# Programmer.net
KiCad netlist of a schematic drawn in Altium Designer
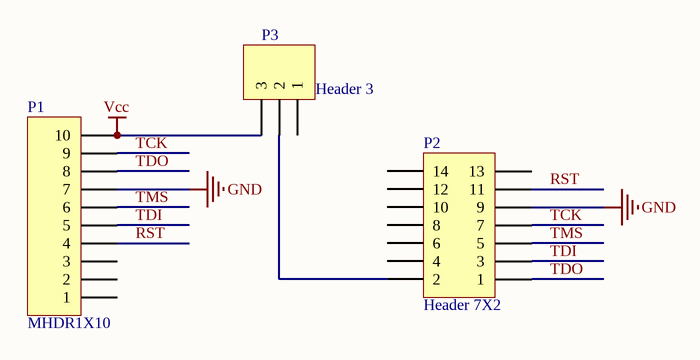
[diagram p0: Programmer.SchDoc]

(export (version "E")
  (design (tool "Eeschema 10.0.6"))
  (components
    (comp (ref "P1")
      (value "MHDR1X10")
      (footprint "MHDR1X10")
      (description "CONN HEADER RT ANG 50POS .050")
      (fields (field (name "MANUFACTURER") "Mill-Max Manufacturing Corp."))
      (libsource (lib "Miscellaneous Connectors") (part "MHDR1X10"))
    )
    (comp (ref "P2")
      (value "Header 7X2")
      (footprint "HDR2X7")
      (description "Header, 7-Pin, Dual row")
      (fields
        (field (name "MANUFACTURER") "Molex Connector Corporation")
        (field (name "PART NUMBER") "90131-0767")
      )
      (libsource (lib "Miscellaneous Connectors") (part "Header 7X2"))
    )
    (comp (ref "P3")
      (value "Header 3")
      (footprint "HDR1X3")
      (description "Header, 3-Pin")
      (fields (field (name "PUBLISHER") "Altium Limited"))
      (libsource (lib "Miscellaneous Connectors") (part "Header 3"))
    )
  )
  (nets
    (net (code "1") (name "/RST") (class "Default")
      (node (ref "P1") (pin "4") (pinfunction "4_4") (pintype "passive"))
      (node (ref "P2") (pin "11") (pinfunction "11_11") (pintype "passive"))
    )
    (net (code "2") (name "/TCK") (class "Default")
      (node (ref "P1") (pin "9") (pinfunction "9_9") (pintype "passive"))
      (node (ref "P2") (pin "7") (pinfunction "7_7") (pintype "passive"))
    )
    (net (code "3") (name "/TDI") (class "Default")
      (node (ref "P1") (pin "5") (pinfunction "5_5") (pintype "passive"))
      (node (ref "P2") (pin "3") (pinfunction "3_3") (pintype "passive"))
    )
    (net (code "4") (name "/TDO") (class "Default")
      (node (ref "P1") (pin "8") (pinfunction "8_8") (pintype "passive"))
      (node (ref "P2") (pin "1") (pinfunction "1_1") (pintype "passive"))
    )
    (net (code "5") (name "/TMS") (class "Default")
      (node (ref "P1") (pin "6") (pinfunction "6_6") (pintype "passive"))
      (node (ref "P2") (pin "5") (pinfunction "5_5") (pintype "passive"))
    )
    (net (code "6") (name "GND") (class "Default")
      (node (ref "P1") (pin "7") (pinfunction "7_7") (pintype "passive"))
      (node (ref "P2") (pin "9") (pinfunction "9_9") (pintype "passive"))
    )
    (net (code "7") (name "Net-(P2-Pad2)") (class "Default")
      (node (ref "P2") (pin "2") (pinfunction "2_2") (pintype "passive"))
      (node (ref "P3") (pin "2") (pinfunction "2_2") (pintype "passive"))
    )
    (net (code "8") (name "Vcc") (class "Default")
      (node (ref "P1") (pin "10") (pinfunction "10_10") (pintype "passive"))
      (node (ref "P3") (pin "3") (pinfunction "3_3") (pintype "passive"))
    )
    (net (code "9") (name "unconnected-(P1-Pad1)") (class "Default")
      (node (ref "P1") (pin "1") (pinfunction "1_1") (pintype "passive"))
    )
    (net (code "10") (name "unconnected-(P1-Pad2)") (class "Default")
      (node (ref "P1") (pin "2") (pinfunction "2_2") (pintype "passive"))
    )
    (net (code "11") (name "unconnected-(P1-Pad3)") (class "Default")
      (node (ref "P1") (pin "3") (pinfunction "3_3") (pintype "passive"))
    )
    (net (code "12") (name "unconnected-(P2-Pad4)") (class "Default")
      (node (ref "P2") (pin "4") (pinfunction "4_4") (pintype "passive"))
    )
    (net (code "13") (name "unconnected-(P2-Pad6)") (class "Default")
      (node (ref "P2") (pin "6") (pinfunction "6_6") (pintype "passive"))
    )
    (net (code "14") (name "unconnected-(P2-Pad8)") (class "Default")
      (node (ref "P2") (pin "8") (pinfunction "8_8") (pintype "passive"))
    )
    (net (code "15") (name "unconnected-(P2-Pad10)") (class "Default")
      (node (ref "P2") (pin "10") (pinfunction "10_10") (pintype "passive"))
    )
    (net (code "16") (name "unconnected-(P2-Pad12)") (class "Default")
      (node (ref "P2") (pin "12") (pinfunction "12_12") (pintype "passive"))
    )
    (net (code "17") (name "unconnected-(P2-Pad13)") (class "Default")
      (node (ref "P2") (pin "13") (pinfunction "13_13") (pintype "passive"))
    )
    (net (code "18") (name "unconnected-(P2-Pad14)") (class "Default")
      (node (ref "P2") (pin "14") (pinfunction "14_14") (pintype "passive"))
    )
    (net (code "19") (name "unconnected-(P3-Pad1)") (class "Default")
      (node (ref "P3") (pin "1") (pinfunction "1_1") (pintype "passive"))
    )
  )
)
